# POWER_IN.net
KiCad netlist of a schematic drawn in Altium Designer
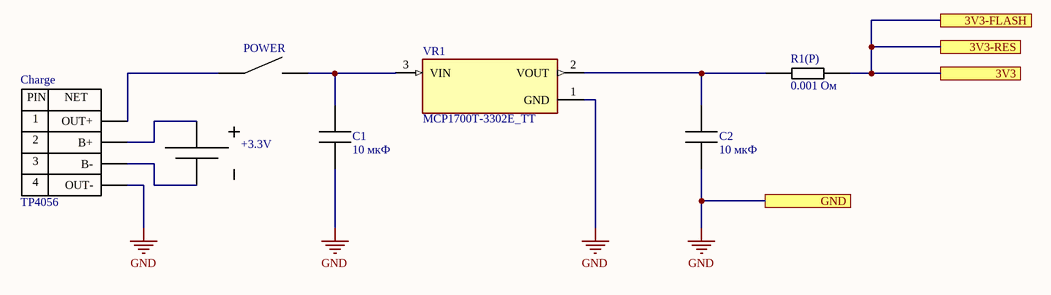
[diagram p0: POWER_IN.SchDoc]

(export (version "E")
  (design (tool "Eeschema 10.0.6"))
  (components
    (comp (ref "+3.3V")
      (value "Battery")
      (footprint "Battery connect")
      (libsource (lib "Schlib1") (part "Battery"))
    )
    (comp (ref "C1")
      (value "10 мкФ")
      (footprint "Murata GRM21BR60J106K")
      (description "Murata GRM21BR60J106K")
      (libsource (lib "Schlib1") (part "Murata GRM21BR60J106K"))
    )
    (comp (ref "C2")
      (value "10 мкФ")
      (footprint "Murata GRM21BR60J106K")
      (description "Murata GRM21BR60J106K")
      (libsource (lib "Schlib1") (part "Murata GRM21BR60J106K"))
    )
    (comp (ref "Charge") (value "TP4056") (footprint "TP4056") (libsource (lib "Schlib1") (part "TP4056")))
    (comp (ref "POWER")
      (value "SMRS-101-1C2")
      (footprint "Button")
      (libsource (lib "Schlib1") (part "Button"))
    )
    (comp (ref "R1(P)")
      (value "0.001 Ом")
      (footprint "Resistor 0.001")
      (libsource (lib "Schlib1") (part "YAGEO PA2512FKF7W0R001E"))
    )
    (comp (ref "VR1")
      (value "MCP1700T-3302E_TT")
      (footprint "SOT95P237X112-3N")
      (fields (field (name "MF") "Microchip") (field (name "MP") "MCP1700T-3302E/TT"))
      (libsource (lib "MCP1700T-3302E_TT") (part "MCP1700T-3302E_TT"))
    )
  )
  (nets
    (net (code "1") (name "/3V3") (class "Default")
      (node (ref "R1(P)") (pin "2") (pinfunction "7_2") (pintype "passive"))
    )
    (net (code "2") (name "GND") (class "Default")
      (node (ref "C1") (pin "1") (pintype "passive"))
      (node (ref "C2") (pin "1") (pintype "passive"))
      (node (ref "Charge") (pin "4") (pinfunction "OUT-_4") (pintype "passive"))
      (node (ref "VR1") (pin "1") (pinfunction "GND_1") (pintype "power_in"))
    )
    (net (code "3") (name "Net-(+3.3V-47)") (class "Default")
      (node (ref "+3.3V") (pin "2") (pinfunction "47_2") (pintype "passive"))
      (node (ref "Charge") (pin "2") (pinfunction "B+_2") (pintype "passive"))
    )
    (net (code "4") (name "Net-(+3.3V-48)") (class "Default")
      (node (ref "+3.3V") (pin "1") (pinfunction "48_1") (pintype "passive"))
      (node (ref "Charge") (pin "3") (pinfunction "B-_3") (pintype "passive"))
    )
    (net (code "5") (name "Net-(Charge-OUT+)") (class "Default")
      (node (ref "Charge") (pin "1") (pinfunction "OUT+_1") (pintype "passive"))
      (node (ref "POWER") (pin "1") (pinfunction "49_1") (pintype "passive"))
    )
    (net (code "6") (name "Net-(R1(P)-6)") (class "Default")
      (node (ref "C2") (pin "2") (pinfunction "2_2") (pintype "passive"))
      (node (ref "R1(P)") (pin "1") (pinfunction "6_1") (pintype "passive"))
      (node (ref "VR1") (pin "2") (pinfunction "VOUT_2") (pintype "output"))
    )
    (net (code "7") (name "Net-(VR1-VIN)") (class "Default")
      (node (ref "C1") (pin "2") (pinfunction "2_2") (pintype "passive"))
      (node (ref "POWER") (pin "2") (pinfunction "2_2") (pintype "passive"))
      (node (ref "VR1") (pin "3") (pinfunction "VIN_3") (pintype "input"))
    )
  )
)
